# Mini_V1_0.net
KiCad netlist of a schematic drawn in Altium Designer
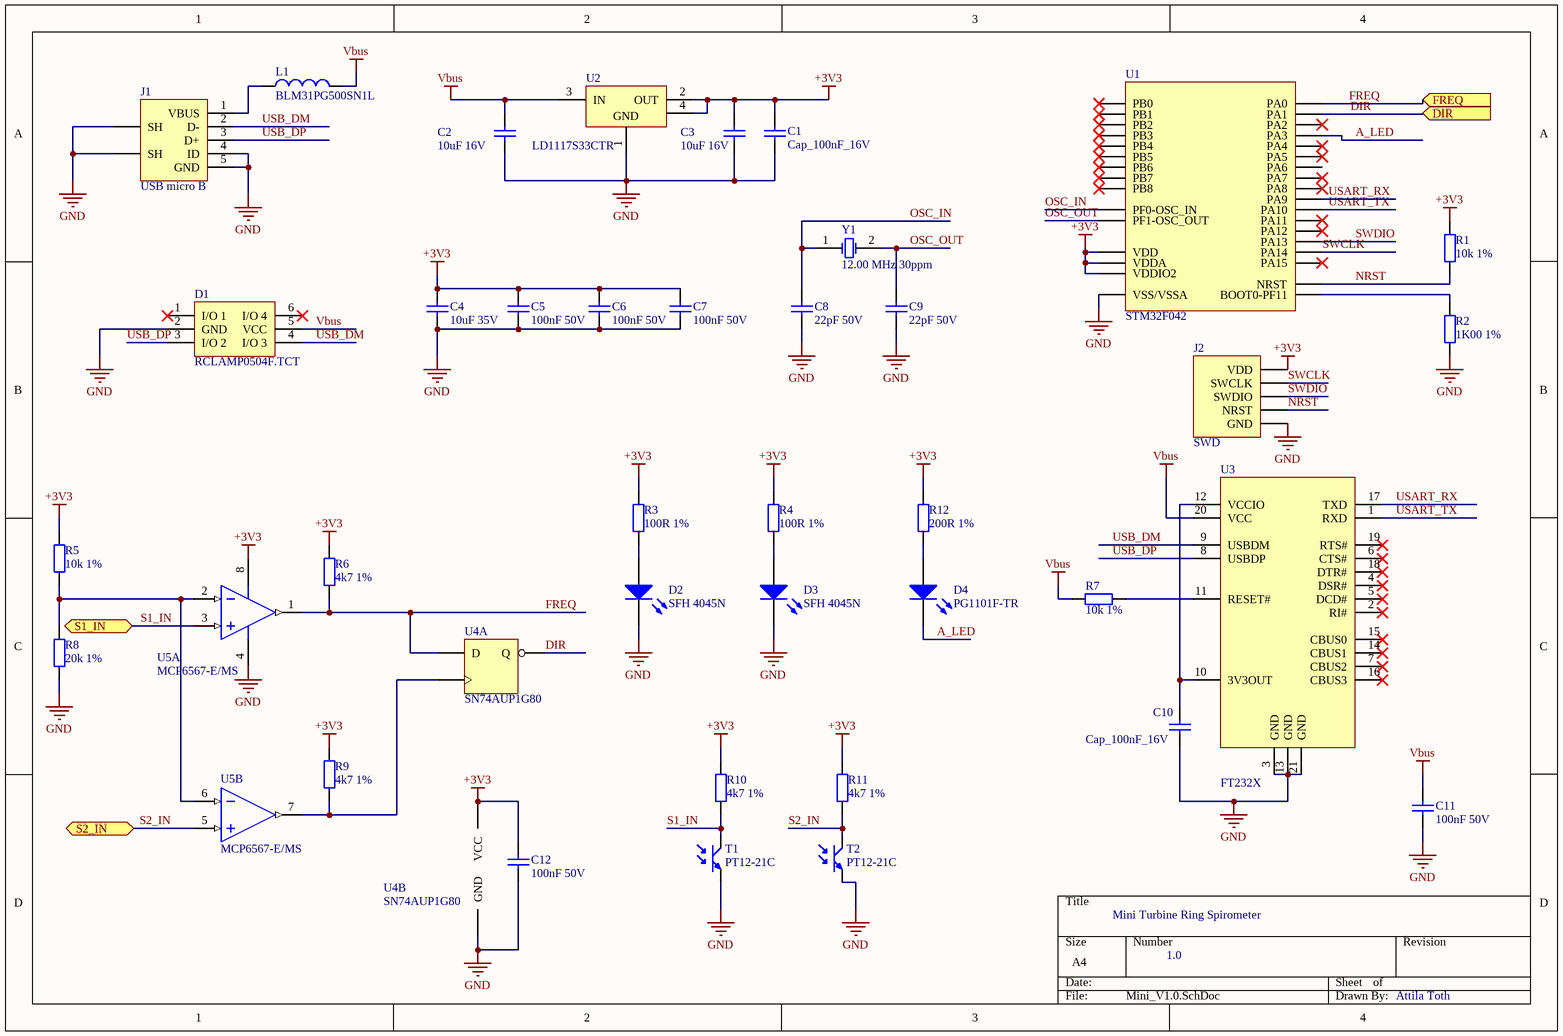
[diagram p0: Mini_V1.0.SchDoc]

(export (version "E")
  (design (tool "Eeschema 10.0.6"))
  (components
    (comp (ref "C1")
      (value "Cap_100nF_16V")
      (footprint "0603_CAP")
      (description "100nF 0603 10% 16V X7R CC0603KPX7R7BB104 (YAG) [82-04-85]")
      (libsource (lib "passive") (part "Cap_100nF_16V"))
    )
    (comp (ref "C2")
      (value "10uF 16V")
      (footprint "1206_CAP")
      (description "10uF 1206 10% 16V X7R CL31B106KOHNNNE (SAM) [82-08-01]")
      (fields (field (name "Comment") "Cap_10uF_16V"))
      (libsource (lib "passive") (part "Cap_10uF_16V"))
    )
    (comp (ref "C3")
      (value "10uF 16V")
      (footprint "1206_CAP")
      (description "10uF 1206 10% 16V X7R CL31B106KOHNNNE (SAM) [82-08-01]")
      (fields (field (name "Comment") "Cap_10uF_16V"))
      (libsource (lib "passive") (part "Cap_10uF_16V"))
    )
    (comp (ref "C4")
      (value "10uF 35V")
      (footprint "1206_CAP")
      (description "CAP CER 10UF 35V Y5V 1206")
      (libsource (lib "passive") (part "Cap_10uF"))
    )
    (comp (ref "C5")
      (value "100nF 50V")
      (footprint "0603_CAP")
      (description "100nF 0603 10% 50V X7R CC0603KRX7R9BB104 (YAG) [82-06-23]")
      (libsource (lib "passive") (part "Cap_100nF"))
    )
    (comp (ref "C6")
      (value "100nF 50V")
      (footprint "0603_CAP")
      (description "100nF 0603 10% 50V X7R CC0603KRX7R9BB104 (YAG) [82-06-23]")
      (libsource (lib "passive") (part "Cap_100nF"))
    )
    (comp (ref "C7")
      (value "100nF 50V")
      (footprint "0603_CAP")
      (description "100nF 0603 10% 50V X7R CC0603KRX7R9BB104 (YAG) [82-06-23]")
      (libsource (lib "passive") (part "Cap_100nF"))
    )
    (comp (ref "C8")
      (value "22pF 50V")
      (footprint "0603_CAP")
      (description "22pF 0603 5% 50V NP0 CC0603JRNPO9BN220 (YAG) [82-02-18]")
      (libsource (lib "passive") (part "Cap_22pF"))
    )
    (comp (ref "C9")
      (value "22pF 50V")
      (footprint "0603_CAP")
      (description "22pF 0603 5% 50V NP0 CC0603JRNPO9BN220 (YAG) [82-02-18]")
      (libsource (lib "passive") (part "Cap_22pF"))
    )
    (comp (ref "C10")
      (value "Cap_100nF_16V")
      (footprint "0603_CAP")
      (description "100nF 0603 10% 16V X7R CC0603KPX7R7BB104 (YAG) [82-04-85]")
      (libsource (lib "passive") (part "Cap_100nF_16V"))
    )
    (comp (ref "C11")
      (value "100nF 50V")
      (footprint "0603_CAP")
      (description "100nF 0603 10% 50V X7R CC0603KRX7R9BB104 (YAG) [82-06-23]")
      (libsource (lib "passive") (part "Cap_100nF"))
    )
    (comp (ref "C12")
      (value "100nF 50V")
      (footprint "0603_CAP")
      (description "100nF 0603 10% 50V X7R CC0603KRX7R9BB104 (YAG) [82-06-23]")
      (libsource (lib "passive") (part "Cap_100nF"))
    )
    (comp (ref "D1")
      (value "RCLAMP0504F.TCT")
      (footprint "SC70-6")
      (description "SEMTECH - RCLAMP0504F.TCT - DIODE, TVS, 5V")
      (libsource (lib "active") (part "RCLAMP0504F.TCT"))
    )
    (comp (ref "D2")
      (value "SFH 4045N")
      (footprint "1506_LED_ANGLE")
      (description "SFH 4045N High Power Infrared Emitter (940 nm)")
      (libsource (lib "active") (part "SFH_4045"))
    )
    (comp (ref "D3")
      (value "SFH 4045N")
      (footprint "1506_LED_ANGLE")
      (description "SFH 4045N High Power Infrared Emitter (940 nm)")
      (libsource (lib "active") (part "SFH_4045"))
    )
    (comp (ref "D4")
      (value "PG1101F-TR")
      (footprint "PG1101F")
      (description "LED GREEN CLEAR 1208 R/A SMD")
      (fields (field (name "MANUFACTURER") "Stanley Electric Co"))
      (libsource (lib "active") (part "PG1101F-TR"))
    )
    (comp (ref "J1")
      (value "USB micro B")
      (footprint "USB MICRO-B TOP_SM_MOLEX_47346-0001")
      (description "MOLEX - 548190519 - MINI USB TYPE B, RECEPTACLE, THT")
      (fields (field (name "Comment") "USB Micro B_SM_473461001"))
      (libsource (lib "connector") (part "USB Micro B_SM_473461001"))
    )
    (comp (ref "J2")
      (value "SWD")
      (footprint "HDR1X5")
      (description "STM SWD PROGRAMMER CONNECTOR")
      (libsource (lib "misc") (part "SWD"))
    )
    (comp (ref "L1")
      (value "BLM31PG500SN1L")
      (footprint "1206_IND")
      (description "FERRITE CHIP 50 OHM 3500MA 1206")
      (libsource (lib "passive") (part "Fer_50R@100MHz"))
    )
    (comp (ref "R1")
      (value "10k 1%")
      (footprint "0603_Res")
      (description "10K0 0603 1% CR-03FL7---10K 0.1W (VIK) [80-11-68]")
      (libsource (lib "passive") (part "Res_10k"))
    )
    (comp (ref "R2")
      (value "1K00 1%")
      (footprint "0603_Res")
      (description "1K00 0603 1% RC0603FR-13 1K00 0.1W (YAG) [80-15-07]")
      (libsource (lib "passive") (part "Res_1k"))
    )
    (comp (ref "R3")
      (value "100R 1%")
      (footprint "0603_Res")
      (description "100R 0603 1% CR-03FL7--100R 0.1W (VIK) [80-11-53]")
      (libsource (lib "passive") (part "Res_100R"))
    )
    (comp (ref "R4")
      (value "100R 1%")
      (footprint "0603_Res")
      (description "100R 0603 1% CR-03FL7--100R 0.1W (VIK) [80-11-53]")
      (libsource (lib "passive") (part "Res_100R"))
    )
    (comp (ref "R5")
      (value "10k 1%")
      (footprint "0603_Res")
      (description "10K0 0603 1% CR-03FL7---10K 0.1W (VIK) [80-11-68]")
      (libsource (lib "passive") (part "Res_10k"))
    )
    (comp (ref "R6")
      (value "4k7 1%")
      (footprint "0603_Res")
      (description "4K70 0603 1% CR-03FL7---4K7 0.1W (VIK) [80-11-85]")
      (libsource (lib "passive") (part "Res_4k7"))
    )
    (comp (ref "R7")
      (value "10k 1%")
      (footprint "0603_Res")
      (description "10K0 0603 1% CR-03FL7---10K 0.1W (VIK) [80-11-68]")
      (libsource (lib "") (part "Res_10k_1"))
    )
    (comp (ref "R8")
      (value "20k 1%")
      (footprint "0603_Res")
      (description "20K0 0603 1% CR-03FL7---20K 0.1W (VIK) [80-14-52]")
      (libsource (lib "passive") (part "Res_20k_1%"))
    )
    (comp (ref "R9")
      (value "4k7 1%")
      (footprint "0603_Res")
      (description "4K70 0603 1% CR-03FL7---4K7 0.1W (VIK) [80-11-85]")
      (libsource (lib "passive") (part "Res_4k7"))
    )
    (comp (ref "R10")
      (value "4k7 1%")
      (footprint "0603_Res")
      (description "4K70 0603 1% CR-03FL7---4K7 0.1W (VIK) [80-11-85]")
      (libsource (lib "passive") (part "Res_4k7"))
    )
    (comp (ref "R11")
      (value "4k7 1%")
      (footprint "0603_Res")
      (description "4K70 0603 1% CR-03FL7---4K7 0.1W (VIK) [80-11-85]")
      (libsource (lib "passive") (part "Res_4k7"))
    )
    (comp (ref "R12")
      (value "200R 1%")
      (footprint "0603_Res")
      (description "200R 0603 1% CR-03FL7--200R 0.1W (VIK) [80-14-37]")
      (libsource (lib "passive") (part "Res_200R_1%"))
    )
    (comp (ref "T1")
      (value "PT12-21C")
      (footprint "PTran_side")
      (description "PHOTOTRANSISTOR WATER CLR RA SMD")
      (fields
        (field (name "MANUFACTURER") "Everlight Electronics Co Ltd")
        (field (name "MANUFACTURER PART NUMBER") "PT12-21C/TR8")
      )
      (libsource (lib "active") (part "PT12-21C/TR8"))
    )
    (comp (ref "T2")
      (value "PT12-21C")
      (footprint "PTran_side")
      (description "PHOTOTRANSISTOR WATER CLR RA SMD")
      (fields
        (field (name "MANUFACTURER") "Everlight Electronics Co Ltd")
        (field (name "MANUFACTURER PART NUMBER") "PT12-21C/TR8")
      )
      (libsource (lib "active") (part "PT12-21C/TR8"))
    )
    (comp (ref "U1")
      (value "STM32F042")
      (footprint "QFN65P700X700X100_HS-33N")
      (description "32 Bit Microcontroller, USB Line, ARM Cortex-M0, 48 MHz, 32 KB, 6 KB, 32, UFQFN")
      (fields
        (field (name "MANUFACTURER") "STMICROELECTRONICS")
        (field (name "MANUFACTURER PART NUMBER") "STM32F042K6U6")
      )
      (libsource (lib "ic") (part "STM32F042K6U6"))
    )
    (comp (ref "U2")
      (value "LD1117S33CTR")
      (footprint "SOT-223")
      (description "LD1117S33CTR (STM) FIX 3.3V 0.95A LDO.VOLT.REG. SOT-223 -40+150°C [89-06-98]")
      (fields (field (name "Comment") "LD1117S33CTR-3.3V"))
      (libsource (lib "ic") (part "LD1117S33CTR-3.3V"))
    )
    (comp (ref "U3")
      (value "FT232X")
      (footprint "QFN50P400X400X80_HS-21N")
      (description "FT232RL (FTD) USB UART IC SSOP-28 [89-21-46]")
      (fields (field (name "Comment") "FT231X"))
      (libsource (lib "ic") (part "FT231X"))
    )
    (comp (ref "U4")
      (value "SN74AUP1G80")
      (footprint "SOT23-5")
      (description "TEXAS INSTRUMENTS - SN74AUP1G80DBVR - IC, FLIP-FLOP, DTYPE, CMOS, 5TSOP")
      (fields
        (field (name "MANUFACTURER") "TEXAS INSTRUMENTS")
        (field (name "MANUFACTURER PART NUMBER") "SN74AUP1G80DBVR")
      )
      (libsource (lib "ic") (part "SN74AUP1G80DBVR"))
    )
    (comp (ref "U5")
      (value "MCP6567-E/MS")
      (footprint "MSOP8")
      (description "Analogue Comparator, Dual, Low Power, 2, 34 ns, 1.8V to 5.5V, MSOP, 8")
      (libsource (lib "ic") (part "MCP6567-E/MS"))
    )
    (comp (ref "Y1")
      (value "12.00 MHz 30ppm")
      (footprint "NXK-32")
      (description "12.000000MHz QUARZ HC49/SMD (NSK) ˝30ppm LOW PROFILE SMD [40-01-25]")
      (fields (field (name "Comment") "XTAL_12MHz"))
      (libsource (lib "misc") (part "XTAL_12MHz"))
    )
  )
  (nets
    (net (code "1") (name "+3V3") (class "Default")
      (node (ref "C1") (pin "1") (pinfunction "1_1") (pintype "passive"))
      (node (ref "C12") (pin "2") (pinfunction "2_2") (pintype "passive"))
      (node (ref "C3") (pin "1") (pinfunction "1_1") (pintype "passive"))
      (node (ref "C4") (pin "2") (pinfunction "2_2") (pintype "passive"))
      (node (ref "C5") (pin "2") (pinfunction "2_2") (pintype "passive"))
      (node (ref "C6") (pin "2") (pinfunction "2_2") (pintype "passive"))
      (node (ref "C7") (pin "2") (pinfunction "2_2") (pintype "passive"))
      (node (ref "J2") (pin "1") (pinfunction "VDD_1") (pintype "passive"))
      (node (ref "R1") (pin "2") (pinfunction "2_2") (pintype "passive"))
      (node (ref "R10") (pin "2") (pinfunction "2_2") (pintype "passive"))
      (node (ref "R11") (pin "2") (pinfunction "2_2") (pintype "passive"))
      (node (ref "R12") (pin "2") (pinfunction "2_2") (pintype "passive"))
      (node (ref "R3") (pin "2") (pinfunction "2_2") (pintype "passive"))
      (node (ref "R4") (pin "2") (pinfunction "2_2") (pintype "passive"))
      (node (ref "R5") (pin "2") (pinfunction "2_2") (pintype "passive"))
      (node (ref "R6") (pin "2") (pinfunction "2_2") (pintype "passive"))
      (node (ref "R9") (pin "2") (pinfunction "2_2") (pintype "passive"))
      (node (ref "U1") (pin "1") (pinfunction "VDD_1") (pintype "passive"))
      (node (ref "U1") (pin "17") (pinfunction "VDDIO2_17") (pintype "passive"))
      (node (ref "U1") (pin "5") (pinfunction "VDDA_5") (pintype "passive"))
      (node (ref "U2") (pin "2") (pinfunction "OUT_2") (pintype "passive"))
      (node (ref "U2") (pin "4") (pinfunction "GND_4") (pintype "passive"))
      (node (ref "U4") (pin "5") (pinfunction "VCC_5") (pintype "passive"))
      (node (ref "U5") (pin "8") (pinfunction "VDD_8") (pintype "power_in"))
    )
    (net (code "2") (name "/A_LED") (class "Default")
      (node (ref "D4") (pin "1") (pinfunction "K_1") (pintype "passive"))
      (node (ref "U1") (pin "9") (pinfunction "PA3_9") (pintype "passive"))
    )
    (net (code "3") (name "/DIR") (class "Default")
      (node (ref "U1") (pin "7") (pinfunction "PA1_7") (pintype "passive"))
      (node (ref "U4") (pin "4") (pinfunction "Q_4") (pintype "passive"))
    )
    (net (code "4") (name "/FREQ") (class "Default")
      (node (ref "R6") (pin "1") (pinfunction "1_1") (pintype "passive"))
      (node (ref "U1") (pin "6") (pinfunction "PA0_6") (pintype "passive"))
      (node (ref "U4") (pin "1") (pinfunction "D_1") (pintype "passive"))
      (node (ref "U5") (pin "1") (pinfunction "VOUTA_1") (pintype "output"))
    )
    (net (code "5") (name "/NRST") (class "Default")
      (node (ref "J2") (pin "5") (pinfunction "NRST_5") (pintype "passive"))
      (node (ref "R1") (pin "1") (pinfunction "1_1") (pintype "passive"))
      (node (ref "U1") (pin "4") (pinfunction "NRST_4") (pintype "passive"))
    )
    (net (code "6") (name "/OSC_IN") (class "Default")
      (node (ref "C8") (pin "2") (pinfunction "2_2") (pintype "passive"))
      (node (ref "U1") (pin "2") (pinfunction "PF0-OSC_IN_2") (pintype "passive"))
      (node (ref "Y1") (pin "1") (pinfunction "OSC1_1") (pintype "passive"))
    )
    (net (code "7") (name "/OSC_OUT") (class "Default")
      (node (ref "C9") (pin "2") (pinfunction "2_2") (pintype "passive"))
      (node (ref "U1") (pin "3") (pinfunction "PF1-OSC_OUT_3") (pintype "passive"))
      (node (ref "Y1") (pin "2") (pinfunction "OSC2_2") (pintype "passive"))
    )
    (net (code "8") (name "/S1_IN") (class "Default")
      (node (ref "R10") (pin "1") (pinfunction "1_1") (pintype "passive"))
      (node (ref "T1") (pin "1") (pinfunction "C_1") (pintype "passive"))
      (node (ref "U5") (pin "3") (pinfunction "VINA+_3") (pintype "input"))
    )
    (net (code "9") (name "/S2_IN") (class "Default")
      (node (ref "R11") (pin "1") (pinfunction "1_1") (pintype "passive"))
      (node (ref "T2") (pin "1") (pinfunction "C_1") (pintype "passive"))
      (node (ref "U5") (pin "5") (pinfunction "VINB+_5") (pintype "input"))
    )
    (net (code "10") (name "/SWCLK") (class "Default")
      (node (ref "J2") (pin "2") (pinfunction "SWCLK_2") (pintype "passive"))
      (node (ref "U1") (pin "24") (pinfunction "PA14_24") (pintype "passive"))
    )
    (net (code "11") (name "/SWDIO") (class "Default")
      (node (ref "J2") (pin "4") (pinfunction "SWDIO_4") (pintype "passive"))
      (node (ref "U1") (pin "23") (pinfunction "PA13_23") (pintype "passive"))
    )
    (net (code "12") (name "/USART_RX") (class "Default")
      (node (ref "U1") (pin "19") (pinfunction "PA9_19") (pintype "passive"))
      (node (ref "U3") (pin "17") (pinfunction "TXD_17") (pintype "passive"))
    )
    (net (code "13") (name "/USART_TX") (class "Default")
      (node (ref "U1") (pin "20") (pinfunction "PA10_20") (pintype "passive"))
      (node (ref "U3") (pin "1") (pinfunction "RXD_1") (pintype "passive"))
    )
    (net (code "14") (name "/USB_DM") (class "Default")
      (node (ref "D1") (pin "4") (pinfunction "I/O_3_4") (pintype "passive"))
      (node (ref "J1") (pin "2") (pinfunction "D-_2") (pintype "passive"))
      (node (ref "U3") (pin "9") (pinfunction "USBDM_9") (pintype "passive"))
    )
    (net (code "15") (name "/USB_DP") (class "Default")
      (node (ref "D1") (pin "3") (pinfunction "I/O_2_3") (pintype "passive"))
      (node (ref "J1") (pin "3") (pinfunction "D+_3") (pintype "passive"))
      (node (ref "U3") (pin "8") (pinfunction "USBDP_8") (pintype "passive"))
    )
    (net (code "16") (name "GND") (class "Default")
      (node (ref "C1") (pin "2") (pinfunction "2_2") (pintype "passive"))
      (node (ref "C10") (pin "2") (pinfunction "2_2") (pintype "passive"))
      (node (ref "C11") (pin "1") (pinfunction "1_1") (pintype "passive"))
      (node (ref "C12") (pin "1") (pinfunction "1_1") (pintype "passive"))
      (node (ref "C2") (pin "2") (pinfunction "2_2") (pintype "passive"))
      (node (ref "C3") (pin "2") (pinfunction "2_2") (pintype "passive"))
      (node (ref "C4") (pin "1") (pinfunction "1_1") (pintype "passive"))
      (node (ref "C5") (pin "1") (pinfunction "1_1") (pintype "passive"))
      (node (ref "C6") (pin "1") (pinfunction "1_1") (pintype "passive"))
      (node (ref "C7") (pin "1") (pinfunction "1_1") (pintype "passive"))
      (node (ref "C8") (pin "1") (pinfunction "1_1") (pintype "passive"))
      (node (ref "C9") (pin "1") (pinfunction "1_1") (pintype "passive"))
      (node (ref "D1") (pin "2") (pinfunction "GND_2") (pintype "passive"))
      (node (ref "D2") (pin "1") (pinfunction "K_1") (pintype "passive"))
      (node (ref "D3") (pin "1") (pinfunction "K_1") (pintype "passive"))
      (node (ref "J1") (pin "0") (pinfunction "SH_0") (pintype "passive"))
      (node (ref "J1") (pin "4") (pinfunction "ID_4") (pintype "passive"))
      (node (ref "J1") (pin "5") (pinfunction "GND_5") (pintype "passive"))
      (node (ref "J2") (pin "3") (pinfunction "GND_3") (pintype "passive"))
      (node (ref "R2") (pin "1") (pinfunction "1_1") (pintype "passive"))
      (node (ref "R8") (pin "1") (pinfunction "1_1") (pintype "passive"))
      (node (ref "T1") (pin "2") (pinfunction "E_2") (pintype "passive"))
      (node (ref "T2") (pin "2") (pinfunction "E_2") (pintype "passive"))
      (node (ref "U1") (pin "33") (pinfunction "VSS/VSSA_33") (pintype "passive"))
      (node (ref "U2") (pin "1") (pinfunction "GND_1") (pintype "passive"))
      (node (ref "U3") (pin "13") (pinfunction "GND_13") (pintype "passive"))
      (node (ref "U3") (pin "21") (pinfunction "GND_21") (pintype "passive"))
      (node (ref "U3") (pin "3") (pinfunction "GND_3") (pintype "passive"))
      (node (ref "U4") (pin "3") (pinfunction "GND_3") (pintype "passive"))
      (node (ref "U5") (pin "4") (pinfunction "VSS_4") (pintype "power_in"))
    )
    (net (code "17") (name "Net-(D2-A)") (class "Default")
      (node (ref "D2") (pin "2") (pinfunction "A_2") (pintype "passive"))
      (node (ref "R3") (pin "1") (pinfunction "1_1") (pintype "passive"))
    )
    (net (code "18") (name "Net-(D3-A)") (class "Default")
      (node (ref "D3") (pin "2") (pinfunction "A_2") (pintype "passive"))
      (node (ref "R4") (pin "1") (pinfunction "1_1") (pintype "passive"))
    )
    (net (code "19") (name "Net-(D4-A)") (class "Default")
      (node (ref "D4") (pin "2") (pinfunction "A_2") (pintype "passive"))
      (node (ref "R12") (pin "1") (pinfunction "1_1") (pintype "passive"))
    )
    (net (code "20") (name "Net-(J1-VBUS)") (class "Default")
      (node (ref "J1") (pin "1") (pinfunction "VBUS_1") (pintype "passive"))
      (node (ref "L1") (pin "1") (pinfunction "1_1") (pintype "passive"))
    )
    (net (code "21") (name "Net-(U1-BOOT0-PF11)") (class "Default")
      (node (ref "R2") (pin "2") (pinfunction "2_2") (pintype "passive"))
      (node (ref "U1") (pin "31") (pinfunction "BOOT0-PF11_31") (pintype "passive"))
    )
    (net (code "22") (name "Net-(U3-3V3OUT)") (class "Default")
      (node (ref "C10") (pin "1") (pinfunction "1_1") (pintype "passive"))
      (node (ref "U3") (pin "10") (pinfunction "3V3OUT_10") (pintype "passive"))
      (node (ref "U3") (pin "12") (pinfunction "VCCIO_12") (pintype "passive"))
    )
    (net (code "23") (name "Net-(U3-RESET#)") (class "Default")
      (node (ref "R7") (pin "2") (pinfunction "2_2") (pintype "passive"))
      (node (ref "U3") (pin "11") (pinfunction "RESET#_11") (pintype "passive"))
    )
    (net (code "24") (name "Net-(U4A-CLK)") (class "Default")
      (node (ref "R9") (pin "1") (pinfunction "1_1") (pintype "passive"))
      (node (ref "U4") (pin "2") (pinfunction "CLK_2") (pintype "passive"))
      (node (ref "U5") (pin "7") (pinfunction "VOUTB_7") (pintype "output"))
    )
    (net (code "25") (name "Net-(U5A-VINA-)") (class "Default")
      (node (ref "R5") (pin "1") (pinfunction "1_1") (pintype "passive"))
      (node (ref "R8") (pin "2") (pinfunction "2_2") (pintype "passive"))
      (node (ref "U5") (pin "2") (pinfunction "VINA-_2") (pintype "input"))
      (node (ref "U5") (pin "6") (pinfunction "VINB-_6") (pintype "input"))
    )
    (net (code "26") (name "Vbus") (class "Default")
      (node (ref "C11") (pin "2") (pinfunction "2_2") (pintype "passive"))
      (node (ref "C2") (pin "1") (pinfunction "1_1") (pintype "passive"))
      (node (ref "D1") (pin "5") (pinfunction "VCC_5") (pintype "passive"))
      (node (ref "L1") (pin "2") (pinfunction "2_2") (pintype "passive"))
      (node (ref "R7") (pin "1") (pinfunction "1_1") (pintype "passive"))
      (node (ref "U2") (pin "3") (pinfunction "IN_3") (pintype "passive"))
      (node (ref "U3") (pin "20") (pinfunction "VCC_20") (pintype "passive"))
    )
    (net (code "27") (name "unconnected-(D1-I{slash}O_1-Pad1)") (class "Default")
      (node (ref "D1") (pin "1") (pinfunction "I/O_1_1") (pintype "passive+no_connect"))
    )
    (net (code "28") (name "unconnected-(D1-I{slash}O_4-Pad6)") (class "Default")
      (node (ref "D1") (pin "6") (pinfunction "I/O_4_6") (pintype "passive+no_connect"))
    )
    (net (code "29") (name "unconnected-(U1-PA2-Pad8)") (class "Default")
      (node (ref "U1") (pin "8") (pinfunction "PA2_8") (pintype "passive+no_connect"))
    )
    (net (code "30") (name "unconnected-(U1-PA4-Pad10)") (class "Default")
      (node (ref "U1") (pin "10") (pinfunction "PA4_10") (pintype "passive+no_connect"))
    )
    (net (code "31") (name "unconnected-(U1-PA5-Pad11)") (class "Default")
      (node (ref "U1") (pin "11") (pinfunction "PA5_11") (pintype "passive+no_connect"))
    )
    (net (code "32") (name "unconnected-(U1-PA6-Pad12)") (class "Default")
      (node (ref "U1") (pin "12") (pinfunction "PA6_12") (pintype "passive"))
    )
    (net (code "33") (name "unconnected-(U1-PA7-Pad13)") (class "Default")
      (node (ref "U1") (pin "13") (pinfunction "PA7_13") (pintype "passive+no_connect"))
    )
    (net (code "34") (name "unconnected-(U1-PA8-Pad18)") (class "Default")
      (node (ref "U1") (pin "18") (pinfunction "PA8_18") (pintype "passive+no_connect"))
    )
    (net (code "35") (name "unconnected-(U1-PA11-Pad21)") (class "Default")
      (node (ref "U1") (pin "21") (pinfunction "PA11_21") (pintype "passive+no_connect"))
    )
    (net (code "36") (name "unconnected-(U1-PA12-Pad22)") (class "Default")
      (node (ref "U1") (pin "22") (pinfunction "PA12_22") (pintype "passive+no_connect"))
    )
    (net (code "37") (name "unconnected-(U1-PA15-Pad25)") (class "Default")
      (node (ref "U1") (pin "25") (pinfunction "PA15_25") (pintype "passive+no_connect"))
    )
    (net (code "38") (name "unconnected-(U1-PB0-Pad14)") (class "Default")
      (node (ref "U1") (pin "14") (pinfunction "PB0_14") (pintype "passive+no_connect"))
    )
    (net (code "39") (name "unconnected-(U1-PB1-Pad15)") (class "Default")
      (node (ref "U1") (pin "15") (pinfunction "PB1_15") (pintype "passive+no_connect"))
    )
    (net (code "40") (name "unconnected-(U1-PB2-Pad16)") (class "Default")
      (node (ref "U1") (pin "16") (pinfunction "PB2_16") (pintype "passive+no_connect"))
    )
    (net (code "41") (name "unconnected-(U1-PB3-Pad26)") (class "Default")
      (node (ref "U1") (pin "26") (pinfunction "PB3_26") (pintype "passive+no_connect"))
    )
    (net (code "42") (name "unconnected-(U1-PB4-Pad27)") (class "Default")
      (node (ref "U1") (pin "27") (pinfunction "PB4_27") (pintype "passive+no_connect"))
    )
    (net (code "43") (name "unconnected-(U1-PB5-Pad28)") (class "Default")
      (node (ref "U1") (pin "28") (pinfunction "PB5_28") (pintype "passive+no_connect"))
    )
    (net (code "44") (name "unconnected-(U1-PB6-Pad29)") (class "Default")
      (node (ref "U1") (pin "29") (pinfunction "PB6_29") (pintype "passive+no_connect"))
    )
    (net (code "45") (name "unconnected-(U1-PB7-Pad30)") (class "Default")
      (node (ref "U1") (pin "30") (pinfunction "PB7_30") (pintype "passive+no_connect"))
    )
    (net (code "46") (name "unconnected-(U1-PB8-Pad32)") (class "Default")
      (node (ref "U1") (pin "32") (pinfunction "PB8_32") (pintype "passive+no_connect"))
    )
    (net (code "47") (name "unconnected-(U3-CBUS0-Pad15)") (class "Default")
      (node (ref "U3") (pin "15") (pinfunction "CBUS0_15") (pintype "passive+no_connect"))
    )
    (net (code "48") (name "unconnected-(U3-CBUS1-Pad14)") (class "Default")
      (node (ref "U3") (pin "14") (pinfunction "CBUS1_14") (pintype "passive+no_connect"))
    )
    (net (code "49") (name "unconnected-(U3-CBUS2-Pad7)") (class "Default")
      (node (ref "U3") (pin "7") (pinfunction "CBUS2_7") (pintype "passive+no_connect"))
    )
    (net (code "50") (name "unconnected-(U3-CBUS3-Pad16)") (class "Default")
      (node (ref "U3") (pin "16") (pinfunction "CBUS3_16") (pintype "passive+no_connect"))
    )
    (net (code "51") (name "unconnected-(U3-CTS#-Pad6)") (class "Default")
      (node (ref "U3") (pin "6") (pinfunction "CTS#_6") (pintype "passive+no_connect"))
    )
    (net (code "52") (name "unconnected-(U3-DCD#-Pad5)") (class "Default")
      (node (ref "U3") (pin "5") (pinfunction "DCD#_5") (pintype "passive+no_connect"))
    )
    (net (code "53") (name "unconnected-(U3-DSR#-Pad4)") (class "Default")
      (node (ref "U3") (pin "4") (pinfunction "DSR#_4") (pintype "passive+no_connect"))
    )
    (net (code "54") (name "unconnected-(U3-DTR#-Pad18)") (class "Default")
      (node (ref "U3") (pin "18") (pinfunction "DTR#_18") (pintype "passive+no_connect"))
    )
    (net (code "55") (name "unconnected-(U3-RI#-Pad2)") (class "Default")
      (node (ref "U3") (pin "2") (pinfunction "RI#_2") (pintype "passive+no_connect"))
    )
    (net (code "56") (name "unconnected-(U3-RTS#-Pad19)") (class "Default")
      (node (ref "U3") (pin "19") (pinfunction "RTS#_19") (pintype "passive+no_connect"))
    )
  )
)
